# esp8266_ir_blaster.net
KiCad netlist of a schematic drawn in EAGLE
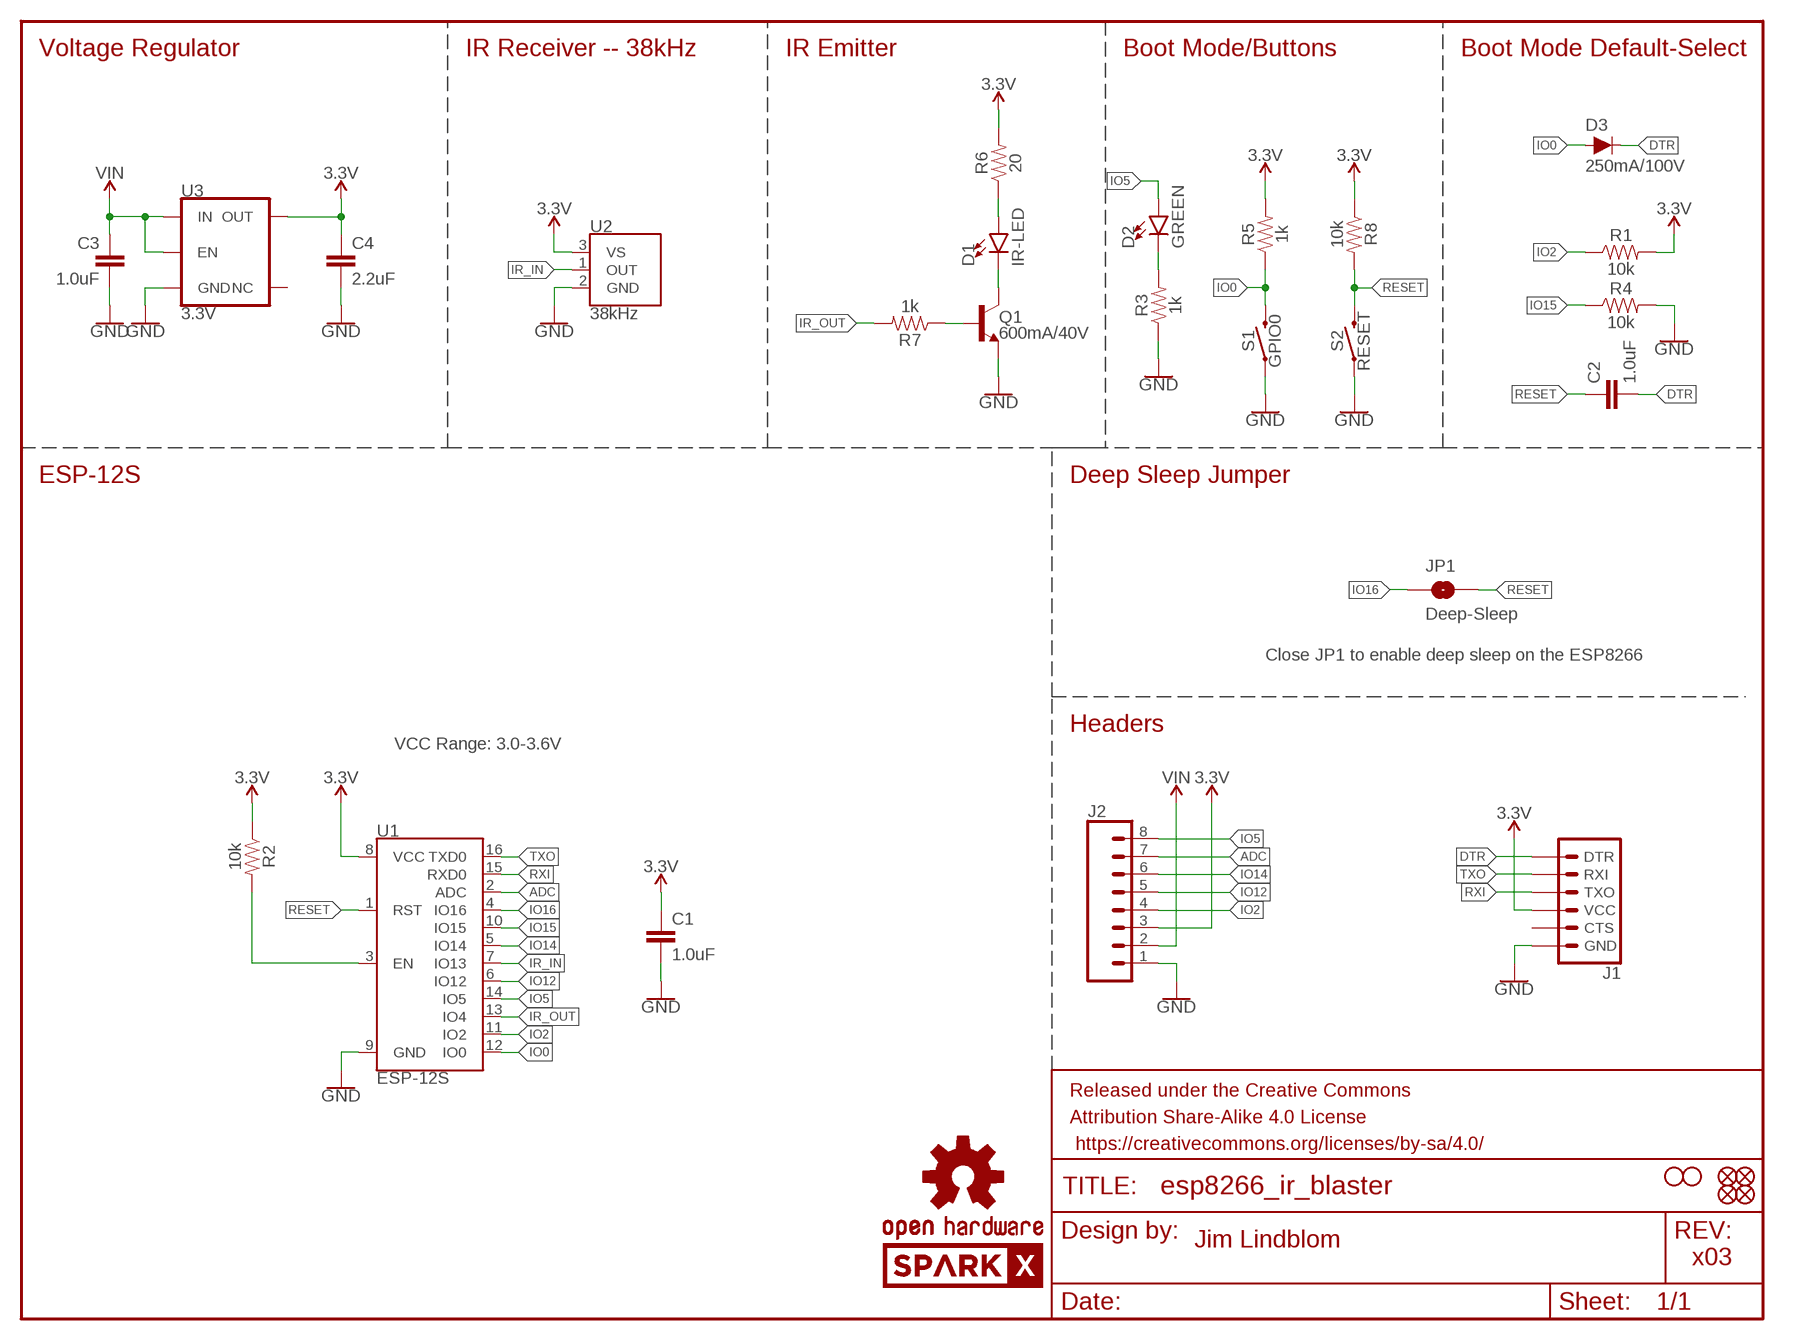
[diagram p0: schematic, sheet 1]

(export (version "E")
  (design (tool "Eeschema 10.0.6"))
  (components
    (comp (ref "C1")
      (value "1.0uF")
      (footprint "eagle-import:0603")
      (libsource (lib "eagle-import") (part "1.0UF-0603-16V-10%"))
    )
    (comp (ref "C2")
      (value "1.0uF")
      (footprint "eagle-import:0603")
      (libsource (lib "eagle-import") (part "1.0UF-0603-16V-10%"))
    )
    (comp (ref "C3")
      (value "1.0uF")
      (footprint "eagle-import:0603")
      (libsource (lib "eagle-import") (part "1.0UF-0603-16V-10%"))
    )
    (comp (ref "C4")
      (value "2.2uF")
      (footprint "eagle-import:0603")
      (libsource (lib "eagle-import") (part "2.2UF-0603-10V-20%"))
    )
    (comp (ref "D1")
      (value "IR-LED")
      (footprint "eagle-import:LTE-302")
      (libsource (lib "eagle-import") (part "LED-IRSIDE_EMITTER"))
    )
    (comp (ref "D2")
      (value "GREEN")
      (footprint "eagle-import:LED-0603")
      (libsource (lib "eagle-import") (part "LED-GREEN0603"))
    )
    (comp (ref "D3")
      (value "250mA/100V")
      (footprint "eagle-import:SOD-323")
      (libsource (lib "eagle-import") (part "DIODE-BAS16J"))
    )
    (comp (ref "FD1")
      (value "FIDUCIALUFIDUCIAL")
      (footprint "eagle-import:FIDUCIAL-MICRO")
      (libsource (lib "eagle-import") (part "FIDUCIALUFIDUCIAL"))
    )
    (comp (ref "FD2")
      (value "FIDUCIALUFIDUCIAL")
      (footprint "eagle-import:FIDUCIAL-MICRO")
      (libsource (lib "eagle-import") (part "FIDUCIALUFIDUCIAL"))
    )
    (comp (ref "FD3")
      (value "FIDUCIALUFIDUCIAL")
      (footprint "eagle-import:FIDUCIAL-MICRO")
      (libsource (lib "eagle-import") (part "FIDUCIALUFIDUCIAL"))
    )
    (comp (ref "FD4")
      (value "FIDUCIALUFIDUCIAL")
      (footprint "eagle-import:FIDUCIAL-MICRO")
      (libsource (lib "eagle-import") (part "FIDUCIALUFIDUCIAL"))
    )
    (comp (ref "FRAME1")
      (value "FRAME-LETTER")
      (footprint "eagle-import:CREATIVE_COMMONS")
      (libsource (lib "eagle-import") (part "FRAME-LETTER"))
    )
    (comp (ref "H1")
      (value "STAND-OFF")
      (footprint "eagle-import:STAND-OFF")
      (libsource (lib "eagle-import") (part "STAND-OFF"))
    )
    (comp (ref "H2")
      (value "STAND-OFF")
      (footprint "eagle-import:STAND-OFF")
      (libsource (lib "eagle-import") (part "STAND-OFF"))
    )
    (comp (ref "J1")
      (value "6_PIN_SERIAL_TARGETNO_SILK")
      (footprint "eagle-import:1X06_NO_SILK")
      (libsource (lib "eagle-import") (part "6_PIN_SERIAL_TARGETNO_SILK"))
    )
    (comp (ref "J2")
      (value "CONN_08NO_SILK_FEMALE_PTH")
      (footprint "eagle-import:1X08_NO_SILK")
      (libsource (lib "eagle-import") (part "CONN_08NO_SILK_FEMALE_PTH"))
    )
    (comp (ref "JP1")
      (value "Deep-Sleep")
      (footprint "eagle-import:SMT-JUMPER_2_NO_NO-SILK")
      (libsource (lib "eagle-import") (part "JUMPER-SMT_2_NO_NO-SILK"))
    )
    (comp (ref "LOGO1")
      (value "OSHW-LOGOS")
      (footprint "eagle-import:OSHW-LOGO-S")
      (libsource (lib "eagle-import") (part "OSHW-LOGOS"))
    )
    (comp (ref "LOGO2")
      (value "SPARKX-LOGO5")
      (footprint "eagle-import:SPARKX-LARGE")
      (libsource (lib "eagle-import") (part "SPARKX-LOGO5"))
    )
    (comp (ref "Q1")
      (value "600mA/40V")
      (footprint "eagle-import:SOT23-3")
      (libsource (lib "eagle-import") (part "TRANS_NPN-MMBT2222AL"))
    )
    (comp (ref "R1")
      (value "10k")
      (footprint "eagle-import:0603")
      (libsource (lib "eagle-import") (part "10KOHM-0603-1/10W-1%"))
    )
    (comp (ref "R2")
      (value "10k")
      (footprint "eagle-import:0603")
      (libsource (lib "eagle-import") (part "10KOHM-0603-1/10W-1%"))
    )
    (comp (ref "R3")
      (value "1k")
      (footprint "eagle-import:0603")
      (libsource (lib "eagle-import") (part "1KOHM-0603-1/10W-1%"))
    )
    (comp (ref "R4")
      (value "10k")
      (footprint "eagle-import:0603")
      (libsource (lib "eagle-import") (part "10KOHM-0603-1/10W-1%"))
    )
    (comp (ref "R5")
      (value "1k")
      (footprint "eagle-import:0603")
      (libsource (lib "eagle-import") (part "1KOHM-0603-1/10W-1%"))
    )
    (comp (ref "R6")
      (value "20")
      (footprint "eagle-import:0603")
      (libsource (lib "eagle-import") (part "20OHM-0603-1/10W-1%"))
    )
    (comp (ref "R7")
      (value "1k")
      (footprint "eagle-import:0603")
      (libsource (lib "eagle-import") (part "1KOHM-0603-1/10W-1%"))
    )
    (comp (ref "R8")
      (value "10k")
      (footprint "eagle-import:0603")
      (libsource (lib "eagle-import") (part "10KOHM-0603-1/10W-1%"))
    )
    (comp (ref "S1")
      (value "GPIO0")
      (footprint "eagle-import:TACTILE_SWITCH_SMD_4.6X2.8MM")
      (libsource (lib "eagle-import") (part "MOMENTARY-SWITCH-SPST-SMD-4.6X2.8MM"))
    )
    (comp (ref "S2")
      (value "RESET")
      (footprint "eagle-import:TACTILE_SWITCH_SMD_4.6X2.8MM")
      (libsource (lib "eagle-import") (part "MOMENTARY-SWITCH-SPST-SMD-4.6X2.8MM"))
    )
    (comp (ref "U1")
      (value "ESP-12S")
      (footprint "eagle-import:ESP-12S")
      (libsource (lib "eagle-import") (part "ESP-12S"))
    )
    (comp (ref "U2")
      (value "38kHz")
      (footprint "eagle-import:TSOP382")
      (libsource (lib "eagle-import") (part "TSOP38238"))
    )
    (comp (ref "U3")
      (value "3.3V")
      (footprint "eagle-import:SOT23-5")
      (libsource (lib "eagle-import") (part "V_REG_AP2112K-3.3V"))
    )
  )
  (nets
    (net (code "1") (name "3.3V") (class "Default")
      (node (ref "C1") (pin "1") (pinfunction "1_1") (pintype "passive"))
      (node (ref "C4") (pin "1") (pinfunction "1_1") (pintype "passive"))
      (node (ref "J1") (pin "4") (pinfunction "VCC_4") (pintype "passive"))
      (node (ref "J2") (pin "3") (pinfunction "3_3") (pintype "passive"))
      (node (ref "R1") (pin "2") (pinfunction "2_2") (pintype "passive"))
      (node (ref "R2") (pin "1") (pinfunction "1_1") (pintype "passive"))
      (node (ref "R5") (pin "2") (pinfunction "2_2") (pintype "passive"))
      (node (ref "R6") (pin "2") (pinfunction "2_2") (pintype "passive"))
      (node (ref "R8") (pin "1") (pinfunction "1_1") (pintype "passive"))
      (node (ref "U1") (pin "8") (pinfunction "VCC_8") (pintype "bidirectional"))
      (node (ref "U2") (pin "3") (pinfunction "VS_3") (pintype "bidirectional"))
      (node (ref "U3") (pin "5") (pinfunction "OUT_5") (pintype "passive"))
    )
    (net (code "2") (name "ADC") (class "Default")
      (node (ref "J2") (pin "7") (pinfunction "7_7") (pintype "passive"))
      (node (ref "U1") (pin "2") (pinfunction "ADC_2") (pintype "bidirectional"))
    )
    (net (code "3") (name "DTR") (class "Default")
      (node (ref "C2") (pin "2") (pinfunction "2_2") (pintype "passive"))
      (node (ref "D3") (pin "C") (pinfunction "C_C") (pintype "passive"))
      (node (ref "J1") (pin "1") (pinfunction "DTR_1") (pintype "passive"))
    )
    (net (code "4") (name "GND") (class "Default")
      (node (ref "C1") (pin "2") (pinfunction "2_2") (pintype "passive"))
      (node (ref "C3") (pin "2") (pinfunction "2_2") (pintype "passive"))
      (node (ref "C4") (pin "2") (pinfunction "2_2") (pintype "passive"))
      (node (ref "J1") (pin "6") (pinfunction "GND_6") (pintype "passive"))
      (node (ref "J2") (pin "1") (pinfunction "1_1") (pintype "passive"))
      (node (ref "Q1") (pin "2") (pinfunction "E_2") (pintype "passive"))
      (node (ref "R3") (pin "1") (pinfunction "1_1") (pintype "passive"))
      (node (ref "R4") (pin "2") (pinfunction "2_2") (pintype "passive"))
      (node (ref "S1") (pin "1") (pinfunction "1_1") (pintype "passive"))
      (node (ref "S1") (pin "2") (pinfunction "1_2") (pintype "passive"))
      (node (ref "S2") (pin "1") (pinfunction "1_1") (pintype "passive"))
      (node (ref "S2") (pin "2") (pinfunction "1_2") (pintype "passive"))
      (node (ref "U1") (pin "9") (pinfunction "GND_9") (pintype "bidirectional"))
      (node (ref "U2") (pin "2") (pinfunction "GND_2") (pintype "bidirectional"))
      (node (ref "U3") (pin "2") (pinfunction "GND_2") (pintype "input"))
    )
    (net (code "5") (name "IO0") (class "Default")
      (node (ref "D3") (pin "A") (pinfunction "A_A") (pintype "passive"))
      (node (ref "R5") (pin "1") (pinfunction "1_1") (pintype "passive"))
      (node (ref "S1") (pin "3") (pinfunction "2_3") (pintype "passive"))
      (node (ref "S1") (pin "4") (pinfunction "2_4") (pintype "passive"))
      (node (ref "U1") (pin "12") (pinfunction "IO0_12") (pintype "bidirectional"))
    )
    (net (code "6") (name "IO2") (class "Default")
      (node (ref "J2") (pin "4") (pinfunction "4_4") (pintype "passive"))
      (node (ref "R1") (pin "1") (pinfunction "1_1") (pintype "passive"))
      (node (ref "U1") (pin "11") (pinfunction "IO2_11") (pintype "bidirectional"))
    )
    (net (code "7") (name "IO5") (class "Default")
      (node (ref "D2") (pin "A") (pinfunction "A_A") (pintype "passive"))
      (node (ref "J2") (pin "8") (pinfunction "8_8") (pintype "passive"))
      (node (ref "U1") (pin "14") (pinfunction "IO5_14") (pintype "bidirectional"))
    )
    (net (code "8") (name "IO12") (class "Default")
      (node (ref "J2") (pin "5") (pinfunction "5_5") (pintype "passive"))
      (node (ref "U1") (pin "6") (pinfunction "IO12_6") (pintype "bidirectional"))
    )
    (net (code "9") (name "IO14") (class "Default")
      (node (ref "J2") (pin "6") (pinfunction "6_6") (pintype "passive"))
      (node (ref "U1") (pin "5") (pinfunction "IO14_5") (pintype "bidirectional"))
    )
    (net (code "10") (name "IO15") (class "Default")
      (node (ref "R4") (pin "1") (pinfunction "1_1") (pintype "passive"))
      (node (ref "U1") (pin "10") (pinfunction "IO15_10") (pintype "bidirectional"))
    )
    (net (code "11") (name "IO16") (class "Default")
      (node (ref "JP1") (pin "1") (pinfunction "1_1") (pintype "passive"))
      (node (ref "U1") (pin "4") (pinfunction "IO16_4") (pintype "bidirectional"))
    )
    (net (code "12") (name "IR_IN") (class "Default")
      (node (ref "U1") (pin "7") (pinfunction "IO13_7") (pintype "bidirectional"))
      (node (ref "U2") (pin "1") (pinfunction "OUT_1") (pintype "bidirectional"))
    )
    (net (code "13") (name "IR_OUT") (class "Default")
      (node (ref "R7") (pin "2") (pinfunction "2_2") (pintype "passive"))
      (node (ref "U1") (pin "13") (pinfunction "IO4_13") (pintype "bidirectional"))
    )
    (net (code "14") (name "Net-(D1-PadA)") (class "Default")
      (node (ref "D1") (pin "A") (pinfunction "A_A") (pintype "passive"))
      (node (ref "R6") (pin "1") (pinfunction "1_1") (pintype "passive"))
    )
    (net (code "15") (name "Net-(D2-PadC)") (class "Default")
      (node (ref "D2") (pin "C") (pinfunction "C_C") (pintype "passive"))
      (node (ref "R3") (pin "2") (pinfunction "2_2") (pintype "passive"))
    )
    (net (code "16") (name "Net-(Q1-B)") (class "Default")
      (node (ref "Q1") (pin "1") (pinfunction "B_1") (pintype "passive"))
      (node (ref "R7") (pin "1") (pinfunction "1_1") (pintype "passive"))
    )
    (net (code "17") (name "Net-(Q1-C)") (class "Default")
      (node (ref "D1") (pin "C") (pinfunction "C_C") (pintype "passive"))
      (node (ref "Q1") (pin "3") (pinfunction "C_3") (pintype "passive"))
    )
    (net (code "18") (name "Net-(U1-EN)") (class "Default")
      (node (ref "R2") (pin "2") (pinfunction "2_2") (pintype "passive"))
      (node (ref "U1") (pin "3") (pinfunction "EN_3") (pintype "bidirectional"))
    )
    (net (code "19") (name "RESET") (class "Default")
      (node (ref "C2") (pin "1") (pinfunction "1_1") (pintype "passive"))
      (node (ref "JP1") (pin "2") (pinfunction "2_2") (pintype "passive"))
      (node (ref "R8") (pin "2") (pinfunction "2_2") (pintype "passive"))
      (node (ref "S2") (pin "3") (pinfunction "2_3") (pintype "passive"))
      (node (ref "S2") (pin "4") (pinfunction "2_4") (pintype "passive"))
      (node (ref "U1") (pin "1") (pinfunction "RST_1") (pintype "bidirectional"))
    )
    (net (code "20") (name "RXI") (class "Default")
      (node (ref "J1") (pin "3") (pinfunction "TXO_3") (pintype "passive"))
      (node (ref "U1") (pin "15") (pinfunction "RXD0_15") (pintype "bidirectional"))
    )
    (net (code "21") (name "TXO") (class "Default")
      (node (ref "J1") (pin "2") (pinfunction "RXI_2") (pintype "passive"))
      (node (ref "U1") (pin "16") (pinfunction "TXD0_16") (pintype "bidirectional"))
    )
    (net (code "22") (name "VIN") (class "Default")
      (node (ref "C3") (pin "1") (pinfunction "1_1") (pintype "passive"))
      (node (ref "J2") (pin "2") (pinfunction "2_2") (pintype "passive"))
      (node (ref "U3") (pin "1") (pinfunction "IN_1") (pintype "input"))
      (node (ref "U3") (pin "3") (pinfunction "EN_3") (pintype "input"))
    )
    (net (code "23") (name "unconnected-(J1-CTS-Pad5)") (class "Default")
      (node (ref "J1") (pin "5") (pinfunction "CTS_5") (pintype "passive"))
    )
    (net (code "24") (name "unconnected-(U3-NC-Pad4)") (class "Default")
      (node (ref "U3") (pin "4") (pinfunction "NC_4") (pintype "no_connect"))
    )
  )
)
